# USB-C_connector.net
KiCad netlist of a schematic drawn in Altium Designer
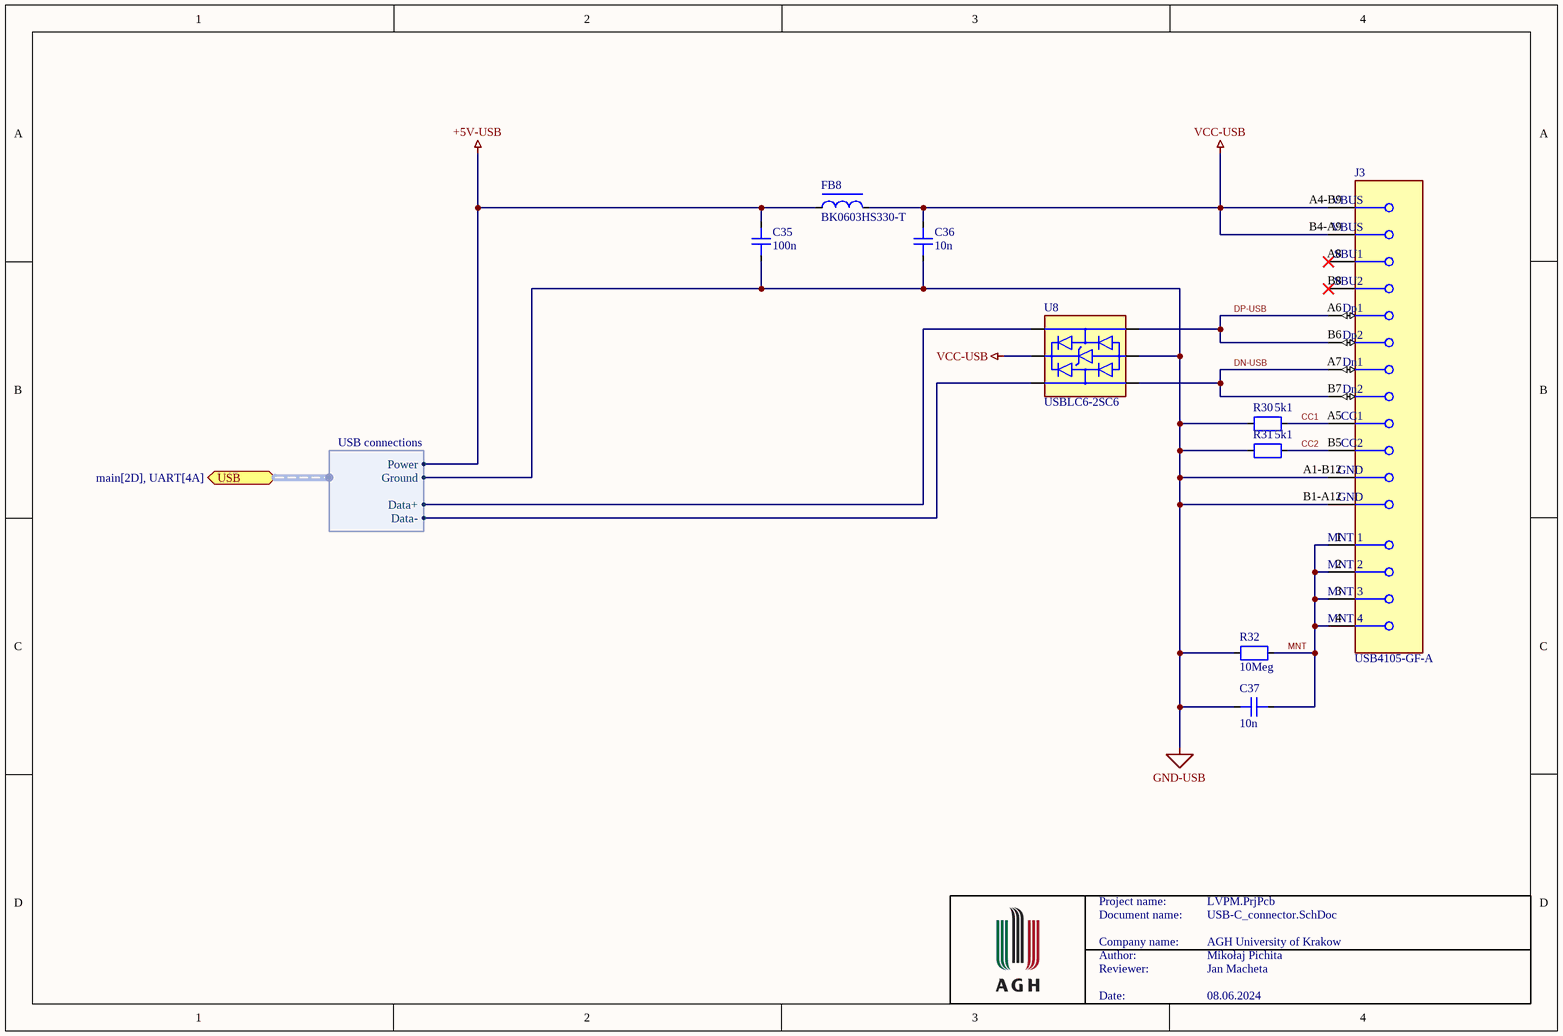
[diagram p0: USB-C_connector.SchDoc]

(export (version "E")
  (design (tool "Eeschema 10.0.6"))
  (components
    (comp (ref "C35")
      (value "100n")
      (footprint "CAP0603")
      (libsource (lib "Integrated_Library_main") (part "Capacitor"))
    )
    (comp (ref "C36")
      (value "10n")
      (footprint "CAP0603")
      (libsource (lib "Integrated_Library_main") (part "Capacitor"))
    )
    (comp (ref "C37")
      (value "10n")
      (footprint "CAP0603")
      (libsource (lib "Integrated_Library_main") (part "Capacitor"))
    )
    (comp (ref "FB8")
      (value "BK0603HS330-T")
      (footprint "FB0402")
      (libsource (lib "Integrated_Library_main") (part "Ferrite Bead"))
    )
    (comp (ref "J3")
      (value "USB4105-GF-A")
      (footprint "FP-USB4105-GF-A-MFG")
      (description "CONN RCPT USB2.0 TYPEC 5A")
      (fields
        (field (name "MANUFACTURER") "GCT")
        (field (name "OCTOPART") "https://octopart.com/usb4105-gf-a-gct-106627878")
      )
      (libsource (lib "Integrated_Library_main") (part "USB4105-GF-A"))
    )
    (comp (ref "R30")
      (value "5k1")
      (footprint "RES0603")
      (libsource (lib "Integrated_Library_main") (part "Resistor"))
    )
    (comp (ref "R31")
      (value "5k1")
      (footprint "RES0603")
      (libsource (lib "Integrated_Library_main") (part "Resistor"))
    )
    (comp (ref "R32")
      (value "10Meg")
      (footprint "RES0603")
      (libsource (lib "Integrated_Library_main") (part "Resistor"))
    )
    (comp (ref "U8")
      (value "USBLC6-2SC6")
      (footprint "SOT95P280X145-6N")
      (description "Very low capacitance ESD protection")
      (libsource (lib "Integrated_Library_main") (part "USBLC6-2SC6"))
    )
  )
  (nets
    (net (code "3") (name "+5V-USB") (class "Default")
      (node (ref "C35") (pin "1") (pintype "passive"))
      (node (ref "FB8") (pin "1") (pintype "passive"))
    )
    (net (code "4") (name "/CC1") (class "Default")
      (node (ref "J3") (pin "A5") (pinfunction "CC1_A5") (pintype "power_in"))
      (node (ref "R30") (pin "2") (pintype "passive"))
    )
    (net (code "5") (name "/CC2") (class "Default")
      (node (ref "J3") (pin "B5") (pinfunction "CC2_B5") (pintype "passive"))
      (node (ref "R31") (pin "2") (pintype "passive"))
    )
    (net (code "6") (name "/DN-USB") (class "Default")
      (node (ref "J3") (pin "A7") (pinfunction "Dn1_A7") (pintype "bidirectional"))
      (node (ref "J3") (pin "B7") (pinfunction "Dn2_B7") (pintype "bidirectional"))
      (node (ref "U8") (pin "1") (pinfunction "I/O1_1") (pintype "passive"))
    )
    (net (code "7") (name "/DP-USB") (class "Default")
      (node (ref "J3") (pin "A6") (pinfunction "Dp1_A6") (pintype "bidirectional"))
      (node (ref "J3") (pin "B6") (pinfunction "Dp2_B6") (pintype "bidirectional"))
      (node (ref "U8") (pin "3") (pinfunction "I/O2_3") (pintype "passive"))
    )
    (net (code "8") (name "/Data+") (class "Default")
      (node (ref "U8") (pin "4") (pinfunction "I/O2_4") (pintype "passive"))
    )
    (net (code "9") (name "/Data-") (class "Default")
      (node (ref "U8") (pin "6") (pinfunction "I/O1_6") (pintype "passive"))
    )
    (net (code "10") (name "/MNT") (class "Default")
      (node (ref "C37") (pin "1") (pintype "passive"))
      (node (ref "J3") (pin "1") (pinfunction "MNT_1_1") (pintype "power_in"))
      (node (ref "J3") (pin "2") (pinfunction "MNT_2_2") (pintype "power_in"))
      (node (ref "J3") (pin "3") (pinfunction "MNT_3_3") (pintype "power_in"))
      (node (ref "J3") (pin "4") (pinfunction "MNT_4_4") (pintype "power_in"))
      (node (ref "R32") (pin "2") (pintype "passive"))
    )
    (net (code "12") (name "GND-USB") (class "Default")
      (node (ref "C35") (pin "2") (pintype "passive"))
      (node (ref "C36") (pin "2") (pintype "passive"))
      (node (ref "C37") (pin "2") (pintype "passive"))
      (node (ref "J3") (pin "A1-B12") (pinfunction "GND_A1-B12") (pintype "power_in"))
      (node (ref "J3") (pin "B1-A12") (pinfunction "GND_B1-A12") (pintype "power_in"))
      (node (ref "R30") (pin "1") (pintype "passive"))
      (node (ref "R31") (pin "1") (pintype "passive"))
      (node (ref "R32") (pin "1") (pintype "passive"))
      (node (ref "U8") (pin "2") (pinfunction "GND_2") (pintype "passive"))
    )
    (net (code "13") (name "VCC-USB") (class "Default")
      (node (ref "C36") (pin "1") (pintype "passive"))
      (node (ref "FB8") (pin "2") (pintype "passive"))
      (node (ref "J3") (pin "A4-B9") (pinfunction "VBUS_A4-B9") (pintype "power_in"))
      (node (ref "J3") (pin "B4-A9") (pinfunction "VBUS_B4-A9") (pintype "power_in"))
      (node (ref "U8") (pin "5") (pinfunction "VBUS_5") (pintype "passive"))
    )
    (net (code "14") (name "unconnected-(J3-SBU1-PadA8)") (class "Default")
      (node (ref "J3") (pin "A8") (pinfunction "SBU1_A8") (pintype "passive+no_connect"))
    )
    (net (code "15") (name "unconnected-(J3-SBU2-PadB8)") (class "Default")
      (node (ref "J3") (pin "B8") (pinfunction "SBU2_B8") (pintype "power_in+no_connect"))
    )
  )
)
